# LedsYOtros.net
KiCad netlist of a schematic drawn in Altium Designer
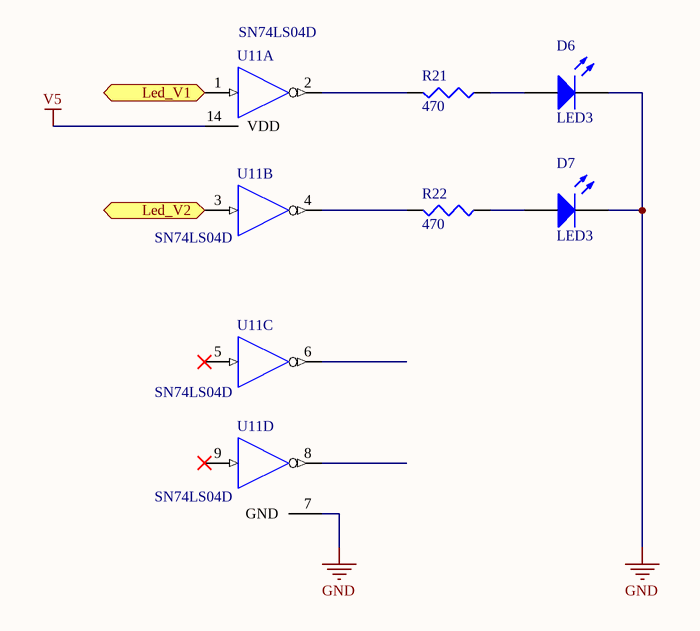
[diagram p0: LedsYOtros.SchDoc]

(export (version "E")
  (design (tool "Eeschema 10.0.6"))
  (components
    (comp (ref "D6")
      (value "LED3")
      (footprint "*0603")
      (description "Typical BLUE SiC LED")
      (fields (field (name "PUBLISHER") "Altium Limited"))
      (libsource (lib "Miscellaneous Devices") (part "LED3"))
    )
    (comp (ref "D7")
      (value "LED3")
      (footprint "*0603")
      (description "Typical BLUE SiC LED")
      (fields (field (name "PUBLISHER") "Altium Limited"))
      (libsource (lib "Miscellaneous Devices") (part "LED3"))
    )
    (comp (ref "R21")
      (value "470")
      (footprint "Custom0805")
      (description "Resistor")
      (fields (field (name "Comment") "Res3") (field (name "PUBLISHER") "Altium Limited"))
      (libsource (lib "Miscellaneous Devices") (part "Res3"))
    )
    (comp (ref "R22")
      (value "470")
      (footprint "Custom0805")
      (description "Resistor")
      (fields (field (name "Comment") "Res3") (field (name "PUBLISHER") "Altium Limited"))
      (libsource (lib "Miscellaneous Devices") (part "Res3"))
    )
    (comp (ref "U11")
      (value "SN74LS04D")
      (footprint "751A-03_N")
      (description "Hex Inverter")
      (fields (field (name "PUBLISHER") "Altium Limited"))
      (libsource (lib "ON Semi Logic Buffer Line Driver") (part "SN74LS04D"))
    )
  )
  (nets
    (net (code "1") (name "/Led_V1") (class "Default")
      (node (ref "U11") (pin "1") (pinfunction "IN_1") (pintype "input"))
    )
    (net (code "2") (name "/Led_V2") (class "Default")
      (node (ref "U11") (pin "3") (pinfunction "IN_3") (pintype "input"))
    )
    (net (code "3") (name "GND") (class "Default")
      (node (ref "D6") (pin "2") (pinfunction "K_2") (pintype "passive"))
      (node (ref "D7") (pin "2") (pinfunction "K_2") (pintype "passive"))
      (node (ref "U11") (pin "7") (pinfunction "GND_7") (pintype "power_in"))
    )
    (net (code "4") (name "Net-(D6-A)") (class "Default")
      (node (ref "D6") (pin "1") (pinfunction "A_1") (pintype "passive"))
      (node (ref "R21") (pin "1") (pinfunction "1_1") (pintype "passive"))
    )
    (net (code "5") (name "Net-(D7-A)") (class "Default")
      (node (ref "D7") (pin "1") (pinfunction "A_1") (pintype "passive"))
      (node (ref "R22") (pin "1") (pinfunction "1_1") (pintype "passive"))
    )
    (net (code "6") (name "Net-(U11A-~{OUT})") (class "Default")
      (node (ref "R21") (pin "2") (pinfunction "2_2") (pintype "passive"))
      (node (ref "U11") (pin "2") (pinfunction "~{OUT}_2") (pintype "output"))
    )
    (net (code "7") (name "Net-(U11B-~{OUT})") (class "Default")
      (node (ref "R22") (pin "2") (pinfunction "2_2") (pintype "passive"))
      (node (ref "U11") (pin "4") (pinfunction "~{OUT}_4") (pintype "output"))
    )
    (net (code "8") (name "V5") (class "Default")
      (node (ref "U11") (pin "14") (pinfunction "VDD_14") (pintype "power_in"))
    )
    (net (code "9") (name "unconnected-(U11C-IN-Pad5)") (class "Default")
      (node (ref "U11") (pin "5") (pinfunction "IN_5") (pintype "input+no_connect"))
    )
    (net (code "10") (name "unconnected-(U11C-~{OUT}-Pad6)") (class "Default")
      (node (ref "U11") (pin "6") (pinfunction "~{OUT}_6") (pintype "output"))
    )
    (net (code "11") (name "unconnected-(U11D-IN-Pad9)") (class "Default")
      (node (ref "U11") (pin "9") (pinfunction "IN_9") (pintype "input+no_connect"))
    )
    (net (code "12") (name "unconnected-(U11D-~{OUT}-Pad8)") (class "Default")
      (node (ref "U11") (pin "8") (pinfunction "~{OUT}_8") (pintype "output"))
    )
  )
)
